# autostepper.net
KiCad netlist of a schematic drawn in EAGLE
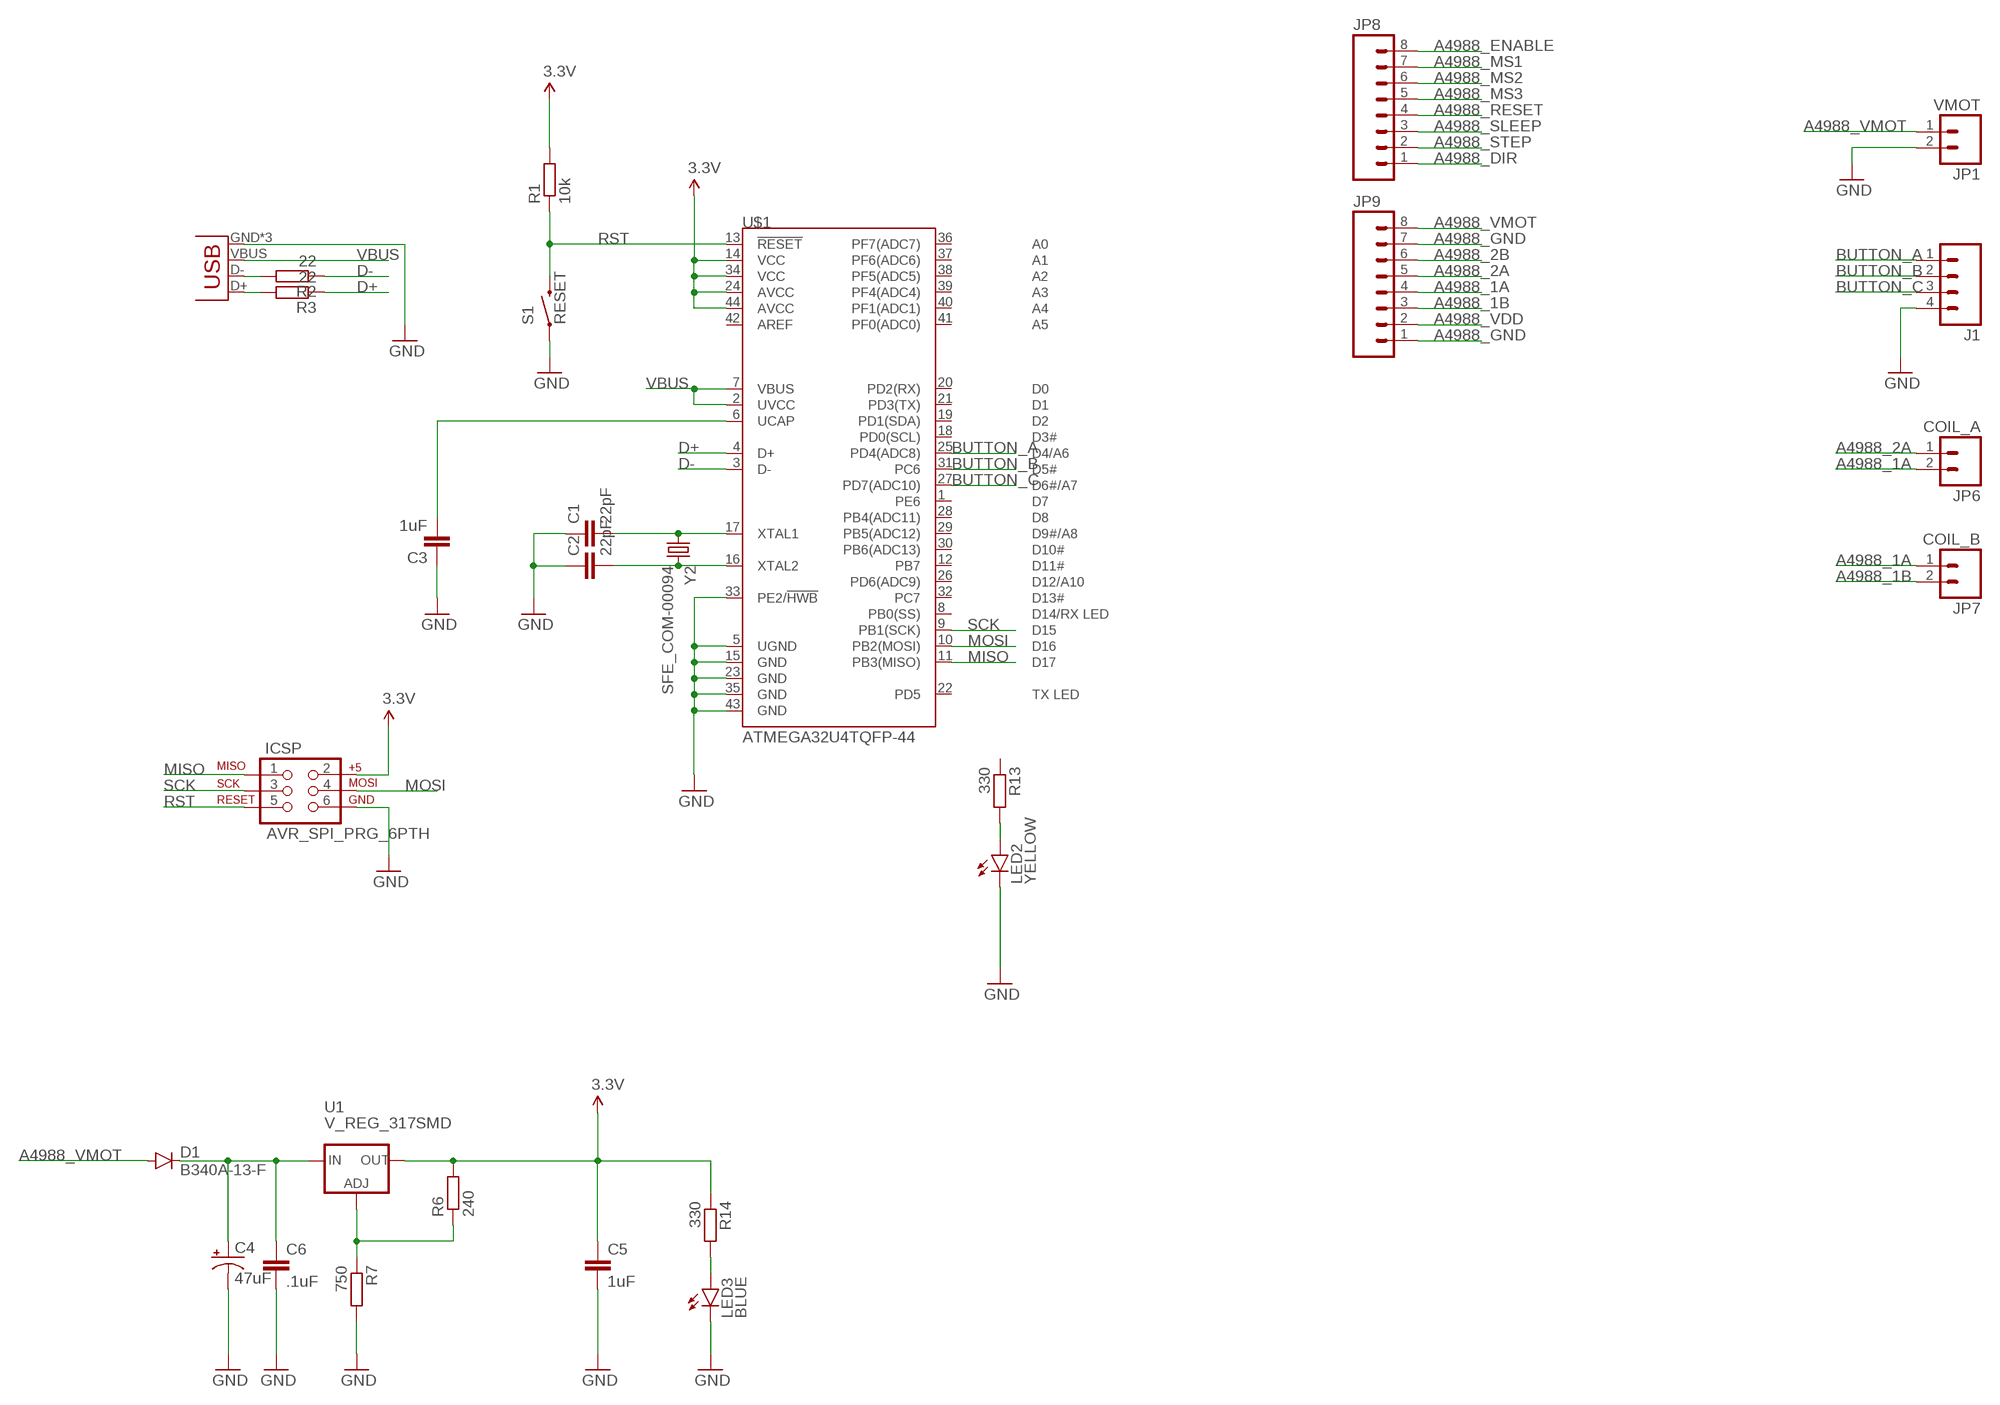
[diagram p0: schematic, sheet 1]

(export (version "E")
  (design (tool "Eeschema 10.0.6"))
  (components
    (comp (ref "C1")
      (value "22pF")
      (footprint "eagle-import:1206")
      (libsource (lib "eagle-import") (part "CAP1206"))
    )
    (comp (ref "C2")
      (value "22pF")
      (footprint "eagle-import:1206")
      (libsource (lib "eagle-import") (part "CAP1206"))
    )
    (comp (ref "C3")
      (value "1uF")
      (footprint "eagle-import:1206")
      (libsource (lib "eagle-import") (part "CAP1206"))
    )
    (comp (ref "C4")
      (value "47uF")
      (footprint "eagle-import:PANASONIC_D")
      (libsource (lib "eagle-import") (part "CAP_POLD"))
    )
    (comp (ref "C5")
      (value "1uF")
      (footprint "eagle-import:1206")
      (libsource (lib "eagle-import") (part "CAP1206"))
    )
    (comp (ref "C6")
      (value ".1uF")
      (footprint "eagle-import:1206")
      (libsource (lib "eagle-import") (part "CAP1206"))
    )
    (comp (ref "D1")
      (value "B340A-13-F")
      (footprint "eagle-import:DIODE-HV")
      (libsource (lib "eagle-import") (part "DIODEHV"))
    )
    (comp (ref "ICSP")
      (value "AVR_SPI_PRG_6PTH")
      (footprint "eagle-import:2X3")
      (libsource (lib "eagle-import") (part "AVR_SPI_PRG_6PTH"))
    )
    (comp (ref "J1")
      (value "M04LONGPADS")
      (footprint "eagle-import:1X04_LONGPADS")
      (libsource (lib "eagle-import") (part "M04LONGPADS"))
    )
    (comp (ref "JP1")
      (value "VMOT")
      (footprint "eagle-import:SCREWTERMINAL-5MM-2")
      (libsource (lib "eagle-import") (part "M025MM"))
    )
    (comp (ref "JP2")
      (value "USB-MICROB")
      (footprint "eagle-import:USB-MICROB")
      (libsource (lib "eagle-import") (part "USB-MICROB"))
    )
    (comp (ref "JP6")
      (value "COIL_A")
      (footprint "eagle-import:SCREWTERMINAL-5MM-2")
      (libsource (lib "eagle-import") (part "M025MM"))
    )
    (comp (ref "JP7")
      (value "COIL_B")
      (footprint "eagle-import:SCREWTERMINAL-5MM-2")
      (libsource (lib "eagle-import") (part "M025MM"))
    )
    (comp (ref "JP8")
      (value "M08LONGPADS")
      (footprint "eagle-import:1X08_LONGPADS")
      (libsource (lib "eagle-import") (part "M08LONGPADS"))
    )
    (comp (ref "JP9")
      (value "M08LONGPADS")
      (footprint "eagle-import:1X08_LONGPADS")
      (libsource (lib "eagle-import") (part "M08LONGPADS"))
    )
    (comp (ref "LED2")
      (value "YELLOW")
      (footprint "eagle-import:LED-0603")
      (libsource (lib "eagle-import") (part "LED0603"))
    )
    (comp (ref "LED3")
      (value "BLUE")
      (footprint "eagle-import:LED-0603")
      (libsource (lib "eagle-import") (part "LED0603"))
    )
    (comp (ref "R1")
      (value "10k")
      (footprint "eagle-import:M0805")
      (libsource (lib "eagle-import") (part "R-EU_M0805"))
    )
    (comp (ref "R2")
      (value "22")
      (footprint "eagle-import:M0805")
      (libsource (lib "eagle-import") (part "R-EU_M0805"))
    )
    (comp (ref "R3")
      (value "22")
      (footprint "eagle-import:M0805")
      (libsource (lib "eagle-import") (part "R-EU_M0805"))
    )
    (comp (ref "R6")
      (value "240")
      (footprint "eagle-import:M0805")
      (libsource (lib "eagle-import") (part "R-EU_M0805"))
    )
    (comp (ref "R7")
      (value "750")
      (footprint "eagle-import:M0805")
      (libsource (lib "eagle-import") (part "R-EU_M0805"))
    )
    (comp (ref "R13")
      (value "330")
      (footprint "eagle-import:M0805")
      (libsource (lib "eagle-import") (part "R-EU_M0805"))
    )
    (comp (ref "R14")
      (value "330")
      (footprint "eagle-import:M0805")
      (libsource (lib "eagle-import") (part "R-EU_M0805"))
    )
    (comp (ref "S1")
      (value "RESET")
      (footprint "eagle-import:TACTILE-SWITCH-SMD")
      (libsource (lib "eagle-import") (part "SWITCH-MOMENTARY-2SMD"))
    )
    (comp (ref "U$1")
      (value "ATMEGA32U4TQFP-44")
      (footprint "eagle-import:TQFP44")
      (libsource (lib "eagle-import") (part "ATMEGA32U4TQFP-44"))
    )
    (comp (ref "U1")
      (value "V_REG_317SMD")
      (footprint "eagle-import:SOT223")
      (libsource (lib "eagle-import") (part "V_REG_317SMD"))
    )
    (comp (ref "Y2")
      (value "SFE_COM-00094")
      (footprint "eagle-import:CRYSTAL-SMD-5X3")
      (libsource (lib "eagle-import") (part "CRYSTAL5X3"))
    )
  )
  (nets
    (net (code "1") (name "/A4988_1A") (class "Default")
      (node (ref "JP6") (pin "2") (pinfunction "2_2") (pintype "passive"))
      (node (ref "JP7") (pin "1") (pinfunction "1_1") (pintype "passive"))
      (node (ref "JP9") (pin "4") (pinfunction "4_4") (pintype "passive"))
    )
    (net (code "2") (name "/A4988_1B") (class "Default")
      (node (ref "JP7") (pin "2") (pinfunction "2_2") (pintype "passive"))
      (node (ref "JP9") (pin "3") (pinfunction "3_3") (pintype "passive"))
    )
    (net (code "3") (name "/A4988_2A") (class "Default")
      (node (ref "JP6") (pin "1") (pinfunction "1_1") (pintype "passive"))
      (node (ref "JP9") (pin "5") (pinfunction "5_5") (pintype "passive"))
    )
    (net (code "4") (name "/A4988_2B") (class "Default")
      (node (ref "JP9") (pin "6") (pinfunction "6_6") (pintype "passive"))
    )
    (net (code "5") (name "/A4988_DIR") (class "Default")
      (node (ref "JP8") (pin "1") (pinfunction "1_1") (pintype "passive"))
    )
    (net (code "6") (name "/A4988_ENABLE") (class "Default")
      (node (ref "JP8") (pin "8") (pinfunction "8_8") (pintype "passive"))
    )
    (net (code "7") (name "/A4988_GND") (class "Default")
      (node (ref "JP9") (pin "1") (pinfunction "1_1") (pintype "passive"))
      (node (ref "JP9") (pin "7") (pinfunction "7_7") (pintype "passive"))
    )
    (net (code "8") (name "/A4988_MS1") (class "Default")
      (node (ref "JP8") (pin "7") (pinfunction "7_7") (pintype "passive"))
    )
    (net (code "9") (name "/A4988_MS2") (class "Default")
      (node (ref "JP8") (pin "6") (pinfunction "6_6") (pintype "passive"))
    )
    (net (code "10") (name "/A4988_MS3") (class "Default")
      (node (ref "JP8") (pin "5") (pinfunction "5_5") (pintype "passive"))
    )
    (net (code "11") (name "/A4988_RESET") (class "Default")
      (node (ref "JP8") (pin "4") (pinfunction "4_4") (pintype "passive"))
    )
    (net (code "12") (name "/A4988_SLEEP") (class "Default")
      (node (ref "JP8") (pin "3") (pinfunction "3_3") (pintype "passive"))
    )
    (net (code "13") (name "/A4988_STEP") (class "Default")
      (node (ref "JP8") (pin "2") (pinfunction "2_2") (pintype "passive"))
    )
    (net (code "14") (name "/A4988_VDD") (class "Default")
      (node (ref "JP9") (pin "2") (pinfunction "2_2") (pintype "passive"))
    )
    (net (code "15") (name "/A4988_VMOT") (class "Default")
      (node (ref "D1") (pin "A") (pinfunction "A_A") (pintype "passive"))
      (node (ref "JP1") (pin "1") (pinfunction "1_1") (pintype "passive"))
      (node (ref "JP9") (pin "8") (pinfunction "8_8") (pintype "passive"))
    )
    (net (code "16") (name "/BUTTON_A") (class "Default")
      (node (ref "J1") (pin "1") (pinfunction "1_1") (pintype "passive"))
      (node (ref "U$1") (pin "25") (pinfunction "PD4(ADC8)_25") (pintype "bidirectional"))
    )
    (net (code "17") (name "/BUTTON_B") (class "Default")
      (node (ref "J1") (pin "2") (pinfunction "2_2") (pintype "passive"))
      (node (ref "U$1") (pin "31") (pinfunction "PC6_31") (pintype "bidirectional"))
    )
    (net (code "18") (name "/BUTTON_C") (class "Default")
      (node (ref "J1") (pin "3") (pinfunction "3_3") (pintype "passive"))
      (node (ref "U$1") (pin "27") (pinfunction "PD7(ADC10)_27") (pintype "bidirectional"))
    )
    (net (code "19") (name "/D+") (class "Default")
      (node (ref "R3") (pin "1") (pinfunction "1_1") (pintype "passive"))
      (node (ref "U$1") (pin "4") (pinfunction "D+_4") (pintype "bidirectional"))
    )
    (net (code "20") (name "/D-") (class "Default")
      (node (ref "R2") (pin "1") (pinfunction "1_1") (pintype "passive"))
      (node (ref "U$1") (pin "3") (pinfunction "D-_3") (pintype "bidirectional"))
    )
    (net (code "21") (name "/MISO") (class "Default")
      (node (ref "ICSP") (pin "1") (pinfunction "1_1") (pintype "passive"))
      (node (ref "U$1") (pin "11") (pinfunction "PB3(MISO)_11") (pintype "bidirectional"))
    )
    (net (code "22") (name "/MOSI") (class "Default")
      (node (ref "ICSP") (pin "4") (pinfunction "4_4") (pintype "passive"))
      (node (ref "U$1") (pin "10") (pinfunction "PB2(MOSI)_10") (pintype "bidirectional"))
    )
    (net (code "23") (name "/RST") (class "Default")
      (node (ref "ICSP") (pin "5") (pinfunction "5_5") (pintype "passive"))
      (node (ref "R1") (pin "1") (pinfunction "1_1") (pintype "passive"))
      (node (ref "S1") (pin "3") (pinfunction "2_3") (pintype "passive"))
      (node (ref "U$1") (pin "13") (pinfunction "~{RESET}_13") (pintype "bidirectional"))
    )
    (net (code "24") (name "/SCK") (class "Default")
      (node (ref "ICSP") (pin "3") (pinfunction "3_3") (pintype "passive"))
      (node (ref "U$1") (pin "9") (pinfunction "PB1(SCK)_9") (pintype "bidirectional"))
    )
    (net (code "25") (name "/VBUS") (class "Default")
      (node (ref "JP2") (pin "VBUS") (pinfunction "VBUS_VBUS") (pintype "bidirectional"))
      (node (ref "U$1") (pin "2") (pinfunction "UVCC_2") (pintype "bidirectional"))
      (node (ref "U$1") (pin "7") (pinfunction "VBUS_7") (pintype "bidirectional"))
    )
    (net (code "26") (name "3.3V") (class "Default")
      (node (ref "C5") (pin "1") (pinfunction "1_1") (pintype "passive"))
      (node (ref "ICSP") (pin "2") (pinfunction "2_2") (pintype "passive"))
      (node (ref "R1") (pin "2") (pinfunction "2_2") (pintype "passive"))
      (node (ref "R14") (pin "1") (pinfunction "1_1") (pintype "passive"))
      (node (ref "R6") (pin "2") (pinfunction "2_2") (pintype "passive"))
      (node (ref "U$1") (pin "14") (pinfunction "VCC_14") (pintype "bidirectional"))
      (node (ref "U$1") (pin "24") (pinfunction "AVCC_24") (pintype "bidirectional"))
      (node (ref "U$1") (pin "34") (pinfunction "VCC_34") (pintype "bidirectional"))
      (node (ref "U$1") (pin "44") (pinfunction "AVCC_44") (pintype "bidirectional"))
      (node (ref "U1") (pin "2") (pinfunction "OUT_2") (pintype "output"))
    )
    (net (code "27") (name "GND") (class "Default")
      (node (ref "C1") (pin "1") (pinfunction "1_1") (pintype "passive"))
      (node (ref "C2") (pin "1") (pinfunction "1_1") (pintype "passive"))
      (node (ref "C3") (pin "1") (pinfunction "1_1") (pintype "passive"))
      (node (ref "C4") (pin "-") (pinfunction "-_-") (pintype "passive"))
      (node (ref "C5") (pin "2") (pinfunction "2_2") (pintype "passive"))
      (node (ref "C6") (pin "2") (pinfunction "2_2") (pintype "passive"))
      (node (ref "ICSP") (pin "6") (pinfunction "6_6") (pintype "passive"))
      (node (ref "J1") (pin "4") (pinfunction "4_4") (pintype "passive"))
      (node (ref "JP1") (pin "2") (pinfunction "2_2") (pintype "passive"))
      (node (ref "JP2") (pin "GND") (pinfunction "GND_GND") (pintype "bidirectional"))
      (node (ref "JP2") (pin "MT1") (pinfunction "GND_MT1") (pintype "bidirectional"))
      (node (ref "JP2") (pin "MT2") (pinfunction "GND_MT2") (pintype "bidirectional"))
      (node (ref "LED2") (pin "C") (pinfunction "C_C") (pintype "passive"))
      (node (ref "LED3") (pin "C") (pinfunction "C_C") (pintype "passive"))
      (node (ref "R7") (pin "2") (pinfunction "2_2") (pintype "passive"))
      (node (ref "S1") (pin "1") (pinfunction "1_1") (pintype "passive"))
      (node (ref "U$1") (pin "15") (pinfunction "GND_15") (pintype "bidirectional"))
      (node (ref "U$1") (pin "23") (pinfunction "GND_23") (pintype "bidirectional"))
      (node (ref "U$1") (pin "33") (pinfunction "PE2/~{HWB}_33") (pintype "bidirectional"))
      (node (ref "U$1") (pin "35") (pinfunction "GND_35") (pintype "bidirectional"))
      (node (ref "U$1") (pin "43") (pinfunction "GND_43") (pintype "bidirectional"))
      (node (ref "U$1") (pin "5") (pinfunction "UGND_5") (pintype "bidirectional"))
    )
    (net (code "28") (name "Net-(JP2-PadD+)") (class "Default")
      (node (ref "JP2") (pin "D+") (pinfunction "D+_D+") (pintype "bidirectional"))
      (node (ref "R3") (pin "2") (pinfunction "2_2") (pintype "passive"))
    )
    (net (code "29") (name "Net-(JP2-PadD-)") (class "Default")
      (node (ref "JP2") (pin "D-") (pinfunction "D-_D-") (pintype "bidirectional"))
      (node (ref "R2") (pin "2") (pinfunction "2_2") (pintype "passive"))
    )
    (net (code "30") (name "Net-(LED2-PadA)") (class "Default")
      (node (ref "LED2") (pin "A") (pinfunction "A_A") (pintype "passive"))
      (node (ref "R13") (pin "2") (pinfunction "2_2") (pintype "passive"))
    )
    (net (code "31") (name "Net-(LED3-PadA)") (class "Default")
      (node (ref "LED3") (pin "A") (pinfunction "A_A") (pintype "passive"))
      (node (ref "R14") (pin "2") (pinfunction "2_2") (pintype "passive"))
    )
    (net (code "32") (name "Net-(U$1-UCAP)") (class "Default")
      (node (ref "C3") (pin "2") (pinfunction "2_2") (pintype "passive"))
      (node (ref "U$1") (pin "6") (pinfunction "UCAP_6") (pintype "bidirectional"))
    )
    (net (code "33") (name "Net-(U$1-XTAL1)") (class "Default")
      (node (ref "C1") (pin "2") (pinfunction "2_2") (pintype "passive"))
      (node (ref "U$1") (pin "17") (pinfunction "XTAL1_17") (pintype "bidirectional"))
      (node (ref "Y2") (pin "1") (pinfunction "1_1") (pintype "passive"))
    )
    (net (code "34") (name "Net-(U$1-XTAL2)") (class "Default")
      (node (ref "C2") (pin "2") (pinfunction "2_2") (pintype "passive"))
      (node (ref "U$1") (pin "16") (pinfunction "XTAL2_16") (pintype "bidirectional"))
      (node (ref "Y2") (pin "3") (pinfunction "2_3") (pintype "passive"))
    )
    (net (code "35") (name "Net-(U1-ADJ)") (class "Default")
      (node (ref "R6") (pin "1") (pinfunction "1_1") (pintype "passive"))
      (node (ref "R7") (pin "1") (pinfunction "1_1") (pintype "passive"))
      (node (ref "U1") (pin "1") (pinfunction "ADJ_1") (pintype "input"))
    )
    (net (code "36") (name "Net-(U1-IN)") (class "Default")
      (node (ref "C4") (pin "+") (pinfunction "+_+") (pintype "passive"))
      (node (ref "C6") (pin "1") (pinfunction "1_1") (pintype "passive"))
      (node (ref "D1") (pin "C") (pinfunction "C_C") (pintype "passive"))
      (node (ref "U1") (pin "3") (pinfunction "IN_3") (pintype "input"))
    )
    (net (code "37") (name "unconnected-(R13-Pad1)") (class "Default")
      (node (ref "R13") (pin "1") (pinfunction "1_1") (pintype "passive"))
    )
    (net (code "38") (name "unconnected-(U$1-AREF-Pad42)") (class "Default")
      (node (ref "U$1") (pin "42") (pinfunction "AREF_42") (pintype "bidirectional"))
    )
    (net (code "39") (name "unconnected-(U$1-PB0(SS)-Pad8)") (class "Default")
      (node (ref "U$1") (pin "8") (pinfunction "PB0(SS)_8") (pintype "bidirectional"))
    )
    (net (code "40") (name "unconnected-(U$1-PB4(ADC11)-Pad28)") (class "Default")
      (node (ref "U$1") (pin "28") (pinfunction "PB4(ADC11)_28") (pintype "bidirectional"))
    )
    (net (code "41") (name "unconnected-(U$1-PB5(ADC12)-Pad29)") (class "Default")
      (node (ref "U$1") (pin "29") (pinfunction "PB5(ADC12)_29") (pintype "bidirectional"))
    )
    (net (code "42") (name "unconnected-(U$1-PB6(ADC13)-Pad30)") (class "Default")
      (node (ref "U$1") (pin "30") (pinfunction "PB6(ADC13)_30") (pintype "bidirectional"))
    )
    (net (code "43") (name "unconnected-(U$1-PB7-Pad12)") (class "Default")
      (node (ref "U$1") (pin "12") (pinfunction "PB7_12") (pintype "bidirectional"))
    )
    (net (code "44") (name "unconnected-(U$1-PC7-Pad32)") (class "Default")
      (node (ref "U$1") (pin "32") (pinfunction "PC7_32") (pintype "bidirectional"))
    )
    (net (code "45") (name "unconnected-(U$1-PD0(SCL)-Pad18)") (class "Default")
      (node (ref "U$1") (pin "18") (pinfunction "PD0(SCL)_18") (pintype "bidirectional"))
    )
    (net (code "46") (name "unconnected-(U$1-PD1(SDA)-Pad19)") (class "Default")
      (node (ref "U$1") (pin "19") (pinfunction "PD1(SDA)_19") (pintype "bidirectional"))
    )
    (net (code "47") (name "unconnected-(U$1-PD2(RX)-Pad20)") (class "Default")
      (node (ref "U$1") (pin "20") (pinfunction "PD2(RX)_20") (pintype "bidirectional"))
    )
    (net (code "48") (name "unconnected-(U$1-PD3(TX)-Pad21)") (class "Default")
      (node (ref "U$1") (pin "21") (pinfunction "PD3(TX)_21") (pintype "bidirectional"))
    )
    (net (code "49") (name "unconnected-(U$1-PD5-Pad22)") (class "Default")
      (node (ref "U$1") (pin "22") (pinfunction "PD5_22") (pintype "bidirectional"))
    )
    (net (code "50") (name "unconnected-(U$1-PD6(ADC9)-Pad26)") (class "Default")
      (node (ref "U$1") (pin "26") (pinfunction "PD6(ADC9)_26") (pintype "bidirectional"))
    )
    (net (code "51") (name "unconnected-(U$1-PE6-Pad1)") (class "Default")
      (node (ref "U$1") (pin "1") (pinfunction "PE6_1") (pintype "bidirectional"))
    )
    (net (code "52") (name "unconnected-(U$1-PF0(ADC0)-Pad41)") (class "Default")
      (node (ref "U$1") (pin "41") (pinfunction "PF0(ADC0)_41") (pintype "bidirectional"))
    )
    (net (code "53") (name "unconnected-(U$1-PF1(ADC1)-Pad40)") (class "Default")
      (node (ref "U$1") (pin "40") (pinfunction "PF1(ADC1)_40") (pintype "bidirectional"))
    )
    (net (code "54") (name "unconnected-(U$1-PF4(ADC4)-Pad39)") (class "Default")
      (node (ref "U$1") (pin "39") (pinfunction "PF4(ADC4)_39") (pintype "bidirectional"))
    )
    (net (code "55") (name "unconnected-(U$1-PF5(ADC5)-Pad38)") (class "Default")
      (node (ref "U$1") (pin "38") (pinfunction "PF5(ADC5)_38") (pintype "bidirectional"))
    )
    (net (code "56") (name "unconnected-(U$1-PF6(ADC6)-Pad37)") (class "Default")
      (node (ref "U$1") (pin "37") (pinfunction "PF6(ADC6)_37") (pintype "bidirectional"))
    )
    (net (code "57") (name "unconnected-(U$1-PF7(ADC7)-Pad36)") (class "Default")
      (node (ref "U$1") (pin "36") (pinfunction "PF7(ADC7)_36") (pintype "bidirectional"))
    )
  )
)
